# jtag-adapter-1-5.net
KiCad netlist of a schematic drawn in EAGLE
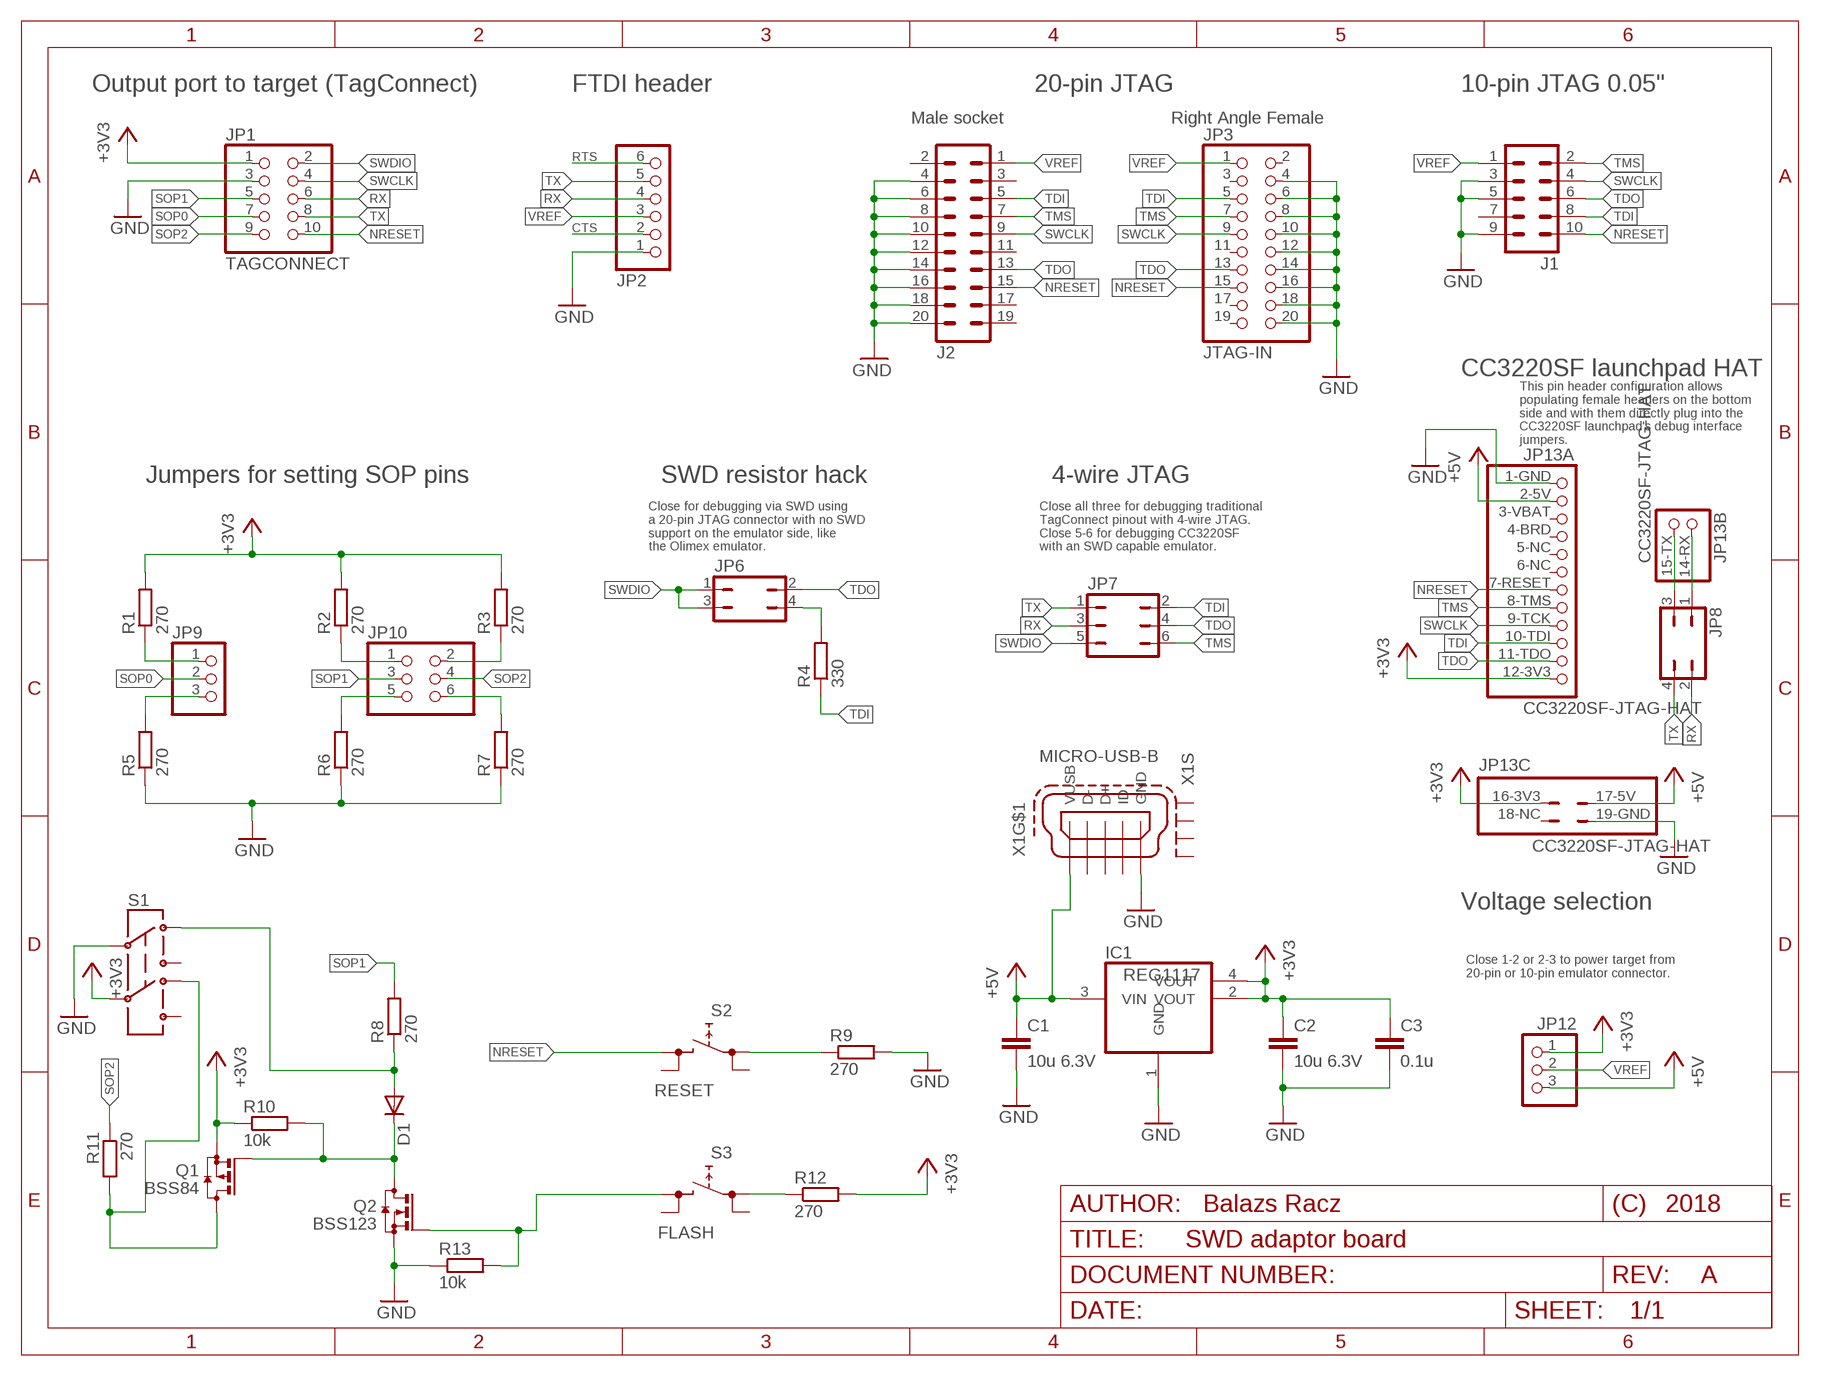
[diagram p0: schematic, sheet 1]

(export (version "E")
  (design (tool "Eeschema 10.0.6"))
  (components
    (comp (ref "C1")
      (value "10u 6.3V")
      (footprint "eagle-import:C0603K")
      (libsource (lib "eagle-import") (part "C-EUC0603K"))
    )
    (comp (ref "C2")
      (value "10u 6.3V")
      (footprint "eagle-import:C0603K")
      (libsource (lib "eagle-import") (part "C-EUC0603K"))
    )
    (comp (ref "C3")
      (value "0.1u")
      (footprint "eagle-import:C0603K")
      (libsource (lib "eagle-import") (part "C-EUC0603K"))
    )
    (comp (ref "D1")
      (value "DIODE-MINIMELF")
      (footprint "eagle-import:MINIMELF")
      (libsource (lib "eagle-import") (part "DIODE-MINIMELF"))
    )
    (comp (ref "IC1")
      (value "REG1117")
      (footprint "eagle-import:SOT223")
      (libsource (lib "eagle-import") (part "REG1117"))
    )
    (comp (ref "J1")
      (value "MA05-2_0.05X0.05")
      (footprint "eagle-import:MA05-2_0.05_X_0.05")
      (libsource (lib "eagle-import") (part "MA05-2_0.05X0.05"))
    )
    (comp (ref "J2")
      (value "MA10-2S")
      (footprint "eagle-import:MA10-2-SHROUDED")
      (libsource (lib "eagle-import") (part "MA10-2S"))
    )
    (comp (ref "JP1")
      (value "TAGCONNECT")
      (footprint "eagle-import:CON10M")
      (libsource (lib "eagle-import") (part "PINHD-2X5CN"))
    )
    (comp (ref "JP2")
      (value "PINHD-1X6")
      (footprint "eagle-import:1X06")
      (libsource (lib "eagle-import") (part "PINHD-1X6"))
    )
    (comp (ref "JP3")
      (value "JTAG-IN")
      (footprint "eagle-import:2X10_90")
      (libsource (lib "eagle-import") (part "PINHD-2X10/90"))
    )
    (comp (ref "JP6")
      (value "JP2Q")
      (footprint "eagle-import:JP2Q")
      (libsource (lib "eagle-import") (part "trainlib_JP2Q"))
    )
    (comp (ref "JP7")
      (value "JP3Q")
      (footprint "eagle-import:JP3Q")
      (libsource (lib "eagle-import") (part "JP3Q"))
    )
    (comp (ref "JP8")
      (value "JP2Q")
      (footprint "eagle-import:JP2Q")
      (libsource (lib "eagle-import") (part "JP2Q"))
    )
    (comp (ref "JP9")
      (value "PINHD-1X3")
      (footprint "eagle-import:1X03")
      (libsource (lib "eagle-import") (part "PINHD-1X3"))
    )
    (comp (ref "JP10")
      (value "PINHD-2X3")
      (footprint "eagle-import:2X03")
      (libsource (lib "eagle-import") (part "PINHD-2X3"))
    )
    (comp (ref "JP12")
      (value "PINHD-1X3")
      (footprint "eagle-import:1X03")
      (libsource (lib "eagle-import") (part "PINHD-1X3"))
    )
    (comp (ref "JP13")
      (value "CC3220SF-JTAG-HAT")
      (footprint "eagle-import:JTAG-LAUNCHPAD-3220SF")
      (libsource (lib "eagle-import") (part "CC3220SF-JTAG-HAT"))
    )
    (comp (ref "Q1")
      (value "BSS84")
      (footprint "eagle-import:SOT23")
      (libsource (lib "eagle-import") (part "BSS84"))
    )
    (comp (ref "Q2")
      (value "BSS123")
      (footprint "eagle-import:SOT23")
      (libsource (lib "eagle-import") (part "BSS123"))
    )
    (comp (ref "R1")
      (value "270")
      (footprint "eagle-import:R0805")
      (libsource (lib "eagle-import") (part "R-EU_R0805"))
    )
    (comp (ref "R2")
      (value "270")
      (footprint "eagle-import:R0805")
      (libsource (lib "eagle-import") (part "R-EU_R0805"))
    )
    (comp (ref "R3")
      (value "270")
      (footprint "eagle-import:R0805")
      (libsource (lib "eagle-import") (part "R-EU_R0805"))
    )
    (comp (ref "R4")
      (value "330")
      (footprint "eagle-import:R0805")
      (libsource (lib "eagle-import") (part "R-EU_R0805"))
    )
    (comp (ref "R5")
      (value "270")
      (footprint "eagle-import:R0805")
      (libsource (lib "eagle-import") (part "R-EU_R0805"))
    )
    (comp (ref "R6")
      (value "270")
      (footprint "eagle-import:R0805")
      (libsource (lib "eagle-import") (part "R-EU_R0805"))
    )
    (comp (ref "R7")
      (value "270")
      (footprint "eagle-import:R0805")
      (libsource (lib "eagle-import") (part "R-EU_R0805"))
    )
    (comp (ref "R8")
      (value "270")
      (footprint "eagle-import:R0805")
      (libsource (lib "eagle-import") (part "R-EU_R0805"))
    )
    (comp (ref "R9")
      (value "270")
      (footprint "eagle-import:R0805")
      (libsource (lib "eagle-import") (part "R-EU_R0805"))
    )
    (comp (ref "R10")
      (value "10k")
      (footprint "eagle-import:R0805")
      (libsource (lib "eagle-import") (part "R-EU_R0805"))
    )
    (comp (ref "R11")
      (value "270")
      (footprint "eagle-import:R0805")
      (libsource (lib "eagle-import") (part "R-EU_R0805"))
    )
    (comp (ref "R12")
      (value "270")
      (footprint "eagle-import:R0805")
      (libsource (lib "eagle-import") (part "R-EU_R0805"))
    )
    (comp (ref "R13")
      (value "10k")
      (footprint "eagle-import:R0805")
      (libsource (lib "eagle-import") (part "R-EU_R0805"))
    )
    (comp (ref "S1")
      (value "SWITCH-DPDTJS202011CQN")
      (footprint "eagle-import:DPDT-2.5X3.2MM")
      (libsource (lib "eagle-import") (part "SWITCH-DPDTJS202011CQN"))
    )
    (comp (ref "S2")
      (value "RESET")
      (footprint "eagle-import:TACTSW-6X6")
      (libsource (lib "eagle-import") (part "TACTSW-6X6S"))
    )
    (comp (ref "S3")
      (value "FLASH")
      (footprint "eagle-import:TACTSW-6X6")
      (libsource (lib "eagle-import") (part "TACTSW-6X6S"))
    )
    (comp (ref "X1")
      (value "MICRO-USB-B")
      (footprint "eagle-import:MICRO-B-PAC")
      (libsource (lib "eagle-import") (part "MICRO-USB-B"))
    )
  )
  (nets
    (net (code "1") (name "+3V3") (class "Default")
      (node (ref "C2") (pin "1") (pinfunction "1_1") (pintype "passive"))
      (node (ref "C3") (pin "1") (pinfunction "1_1") (pintype "passive"))
      (node (ref "IC1") (pin "2") (pinfunction "VOUT_2") (pintype "output"))
      (node (ref "IC1") (pin "4") (pinfunction "VOUT_4") (pintype "output"))
      (node (ref "JP1") (pin "1") (pinfunction "1_1") (pintype "passive"))
      (node (ref "JP12") (pin "1") (pinfunction "1_1") (pintype "passive"))
      (node (ref "JP13") (pin "12-3V3") (pinfunction "12_12-3V3") (pintype "passive"))
      (node (ref "JP13") (pin "16-3V3") (pinfunction "1_16-3V3") (pintype "passive"))
      (node (ref "Q1") (pin "2") (pinfunction "S_2") (pintype "passive"))
      (node (ref "R1") (pin "2") (pinfunction "2_2") (pintype "passive"))
      (node (ref "R10") (pin "1") (pinfunction "1_1") (pintype "passive"))
      (node (ref "R12") (pin "2") (pinfunction "2_2") (pintype "passive"))
      (node (ref "R2") (pin "2") (pinfunction "2_2") (pintype "passive"))
      (node (ref "R3") (pin "2") (pinfunction "2_2") (pintype "passive"))
      (node (ref "S1") (pin "5") (pinfunction "2C_5") (pintype "bidirectional"))
    )
    (net (code "2") (name "+5V") (class "Default")
      (node (ref "C1") (pin "1") (pinfunction "1_1") (pintype "passive"))
      (node (ref "IC1") (pin "3") (pinfunction "VIN_3") (pintype "input"))
      (node (ref "JP12") (pin "3") (pinfunction "3_3") (pintype "passive"))
      (node (ref "JP13") (pin "17-5V") (pinfunction "2_17-5V") (pintype "passive"))
      (node (ref "JP13") (pin "2-5V") (pinfunction "2_2-5V") (pintype "passive"))
      (node (ref "X1") (pin "1") (pinfunction "VUSB_1") (pintype "passive"))
    )
    (net (code "3") (name "/CTS") (class "Default")
      (node (ref "JP2") (pin "2") (pinfunction "2_2") (pintype "passive"))
    )
    (net (code "4") (name "/RTS") (class "Default")
      (node (ref "JP2") (pin "6") (pinfunction "6_6") (pintype "passive"))
    )
    (net (code "5") (name "GND") (class "Default")
      (node (ref "C1") (pin "2") (pinfunction "2_2") (pintype "passive"))
      (node (ref "C2") (pin "2") (pinfunction "2_2") (pintype "passive"))
      (node (ref "C3") (pin "2") (pinfunction "2_2") (pintype "passive"))
      (node (ref "IC1") (pin "1") (pinfunction "GND_1") (pintype "power_in"))
      (node (ref "J1") (pin "3") (pinfunction "3_3") (pintype "passive"))
      (node (ref "J1") (pin "5") (pinfunction "5_5") (pintype "passive"))
      (node (ref "J1") (pin "9") (pinfunction "9_9") (pintype "passive"))
      (node (ref "J2") (pin "10") (pinfunction "10_10") (pintype "passive"))
      (node (ref "J2") (pin "12") (pinfunction "12_12") (pintype "passive"))
      (node (ref "J2") (pin "14") (pinfunction "14_14") (pintype "passive"))
      (node (ref "J2") (pin "16") (pinfunction "16_16") (pintype "passive"))
      (node (ref "J2") (pin "18") (pinfunction "18_18") (pintype "passive"))
      (node (ref "J2") (pin "20") (pinfunction "20_20") (pintype "passive"))
      (node (ref "J2") (pin "4") (pinfunction "4_4") (pintype "passive"))
      (node (ref "J2") (pin "6") (pinfunction "6_6") (pintype "passive"))
      (node (ref "J2") (pin "8") (pinfunction "8_8") (pintype "passive"))
      (node (ref "JP1") (pin "3") (pinfunction "3_3") (pintype "passive"))
      (node (ref "JP13") (pin "1-GND") (pinfunction "1_1-GND") (pintype "passive"))
      (node (ref "JP13") (pin "19-GND") (pinfunction "4_19-GND") (pintype "passive"))
      (node (ref "JP2") (pin "1") (pinfunction "1_1") (pintype "passive"))
      (node (ref "JP3") (pin "10") (pinfunction "10_10") (pintype "passive"))
      (node (ref "JP3") (pin "12") (pinfunction "12_12") (pintype "passive"))
      (node (ref "JP3") (pin "14") (pinfunction "14_14") (pintype "passive"))
      (node (ref "JP3") (pin "16") (pinfunction "16_16") (pintype "passive"))
      (node (ref "JP3") (pin "18") (pinfunction "18_18") (pintype "passive"))
      (node (ref "JP3") (pin "20") (pinfunction "20_20") (pintype "passive"))
      (node (ref "JP3") (pin "4") (pinfunction "4_4") (pintype "passive"))
      (node (ref "JP3") (pin "6") (pinfunction "6_6") (pintype "passive"))
      (node (ref "JP3") (pin "8") (pinfunction "8_8") (pintype "passive"))
      (node (ref "Q2") (pin "2") (pinfunction "S_2") (pintype "passive"))
      (node (ref "R13") (pin "1") (pinfunction "1_1") (pintype "passive"))
      (node (ref "R5") (pin "1") (pinfunction "1_1") (pintype "passive"))
      (node (ref "R6") (pin "1") (pinfunction "1_1") (pintype "passive"))
      (node (ref "R7") (pin "1") (pinfunction "1_1") (pintype "passive"))
      (node (ref "R9") (pin "2") (pinfunction "2_2") (pintype "passive"))
      (node (ref "S1") (pin "2") (pinfunction "1C_2") (pintype "bidirectional"))
      (node (ref "X1") (pin "5") (pinfunction "GND_5") (pintype "passive"))
    )
    (net (code "6") (name "NRESET") (class "Default")
      (node (ref "J1") (pin "10") (pinfunction "10_10") (pintype "passive"))
      (node (ref "J2") (pin "15") (pinfunction "15_15") (pintype "passive"))
      (node (ref "JP1") (pin "10") (pinfunction "10_10") (pintype "passive"))
      (node (ref "JP13") (pin "7-RESET") (pinfunction "7_7-RESET") (pintype "passive"))
      (node (ref "JP3") (pin "15") (pinfunction "15_15") (pintype "passive"))
      (node (ref "S2") (pin "3") (pinfunction "2.1_3") (pintype "passive"))
    )
    (net (code "7") (name "Net-(JP6-Pad4)") (class "Default")
      (node (ref "JP6") (pin "4") (pinfunction "4_4") (pintype "passive"))
      (node (ref "R4") (pin "2") (pinfunction "2_2") (pintype "passive"))
    )
    (net (code "8") (name "Net-(JP9-Pad1)") (class "Default")
      (node (ref "JP9") (pin "1") (pinfunction "1_1") (pintype "passive"))
      (node (ref "R1") (pin "1") (pinfunction "1_1") (pintype "passive"))
    )
    (net (code "9") (name "Net-(JP9-Pad3)") (class "Default")
      (node (ref "JP9") (pin "3") (pinfunction "3_3") (pintype "passive"))
      (node (ref "R5") (pin "2") (pinfunction "2_2") (pintype "passive"))
    )
    (net (code "10") (name "Net-(JP10-Pad1)") (class "Default")
      (node (ref "JP10") (pin "1") (pinfunction "1_1") (pintype "passive"))
      (node (ref "R2") (pin "1") (pinfunction "1_1") (pintype "passive"))
    )
    (net (code "11") (name "Net-(JP10-Pad2)") (class "Default")
      (node (ref "JP10") (pin "2") (pinfunction "2_2") (pintype "passive"))
      (node (ref "R3") (pin "1") (pinfunction "1_1") (pintype "passive"))
    )
    (net (code "12") (name "Net-(JP10-Pad5)") (class "Default")
      (node (ref "JP10") (pin "5") (pinfunction "5_5") (pintype "passive"))
      (node (ref "R6") (pin "2") (pinfunction "2_2") (pintype "passive"))
    )
    (net (code "13") (name "Net-(JP10-Pad6)") (class "Default")
      (node (ref "JP10") (pin "6") (pinfunction "6_6") (pintype "passive"))
      (node (ref "R7") (pin "2") (pinfunction "2_2") (pintype "passive"))
    )
    (net (code "14") (name "Net-(JP13B-1)") (class "Default")
      (node (ref "JP13") (pin "14-RX") (pinfunction "1_14-RX") (pintype "passive"))
      (node (ref "JP8") (pin "1") (pinfunction "1_1") (pintype "passive"))
    )
    (net (code "15") (name "Net-(JP13B-2)") (class "Default")
      (node (ref "JP13") (pin "15-TX") (pinfunction "2_15-TX") (pintype "passive"))
      (node (ref "JP8") (pin "3") (pinfunction "3_3") (pintype "passive"))
    )
    (net (code "16") (name "Net-(Q1-D)") (class "Default")
      (node (ref "Q1") (pin "3") (pinfunction "D_3") (pintype "passive"))
      (node (ref "R11") (pin "2") (pinfunction "2_2") (pintype "passive"))
      (node (ref "S1") (pin "4") (pinfunction "2A_4") (pintype "bidirectional"))
    )
    (net (code "17") (name "Net-(Q1-G)") (class "Default")
      (node (ref "D1") (pin "C") (pinfunction "C_C") (pintype "passive"))
      (node (ref "Q1") (pin "1") (pinfunction "G_1") (pintype "passive"))
      (node (ref "Q2") (pin "3") (pinfunction "D_3") (pintype "passive"))
      (node (ref "R10") (pin "2") (pinfunction "2_2") (pintype "passive"))
    )
    (net (code "18") (name "Net-(Q2-G)") (class "Default")
      (node (ref "Q2") (pin "1") (pinfunction "G_1") (pintype "passive"))
      (node (ref "R13") (pin "2") (pinfunction "2_2") (pintype "passive"))
      (node (ref "S3") (pin "3") (pinfunction "2.1_3") (pintype "passive"))
    )
    (net (code "19") (name "Net-(S1-1A)") (class "Default")
      (node (ref "D1") (pin "A") (pinfunction "A_A") (pintype "passive"))
      (node (ref "R8") (pin "1") (pinfunction "1_1") (pintype "passive"))
      (node (ref "S1") (pin "1") (pinfunction "1A_1") (pintype "bidirectional"))
    )
    (net (code "20") (name "Net-(S2-1.1)") (class "Default")
      (node (ref "R9") (pin "1") (pinfunction "1_1") (pintype "passive"))
      (node (ref "S2") (pin "1") (pinfunction "1.1_1") (pintype "passive"))
    )
    (net (code "21") (name "Net-(S3-1.1)") (class "Default")
      (node (ref "R12") (pin "1") (pinfunction "1_1") (pintype "passive"))
      (node (ref "S3") (pin "1") (pinfunction "1.1_1") (pintype "passive"))
    )
    (net (code "22") (name "RX") (class "Default")
      (node (ref "JP1") (pin "6") (pinfunction "6_6") (pintype "passive"))
      (node (ref "JP2") (pin "4") (pinfunction "4_4") (pintype "passive"))
      (node (ref "JP7") (pin "3") (pinfunction "3_3") (pintype "passive"))
      (node (ref "JP8") (pin "2") (pinfunction "2_2") (pintype "passive"))
    )
    (net (code "23") (name "SOP0") (class "Default")
      (node (ref "JP1") (pin "7") (pinfunction "7_7") (pintype "passive"))
      (node (ref "JP9") (pin "2") (pinfunction "2_2") (pintype "passive"))
    )
    (net (code "24") (name "SOP1") (class "Default")
      (node (ref "JP1") (pin "5") (pinfunction "5_5") (pintype "passive"))
      (node (ref "JP10") (pin "3") (pinfunction "3_3") (pintype "passive"))
      (node (ref "R8") (pin "2") (pinfunction "2_2") (pintype "passive"))
    )
    (net (code "25") (name "SOP2") (class "Default")
      (node (ref "JP1") (pin "9") (pinfunction "9_9") (pintype "passive"))
      (node (ref "JP10") (pin "4") (pinfunction "4_4") (pintype "passive"))
      (node (ref "R11") (pin "1") (pinfunction "1_1") (pintype "passive"))
    )
    (net (code "26") (name "SWCLK") (class "Default")
      (node (ref "J1") (pin "4") (pinfunction "4_4") (pintype "passive"))
      (node (ref "J2") (pin "9") (pinfunction "9_9") (pintype "passive"))
      (node (ref "JP1") (pin "4") (pinfunction "4_4") (pintype "passive"))
      (node (ref "JP13") (pin "9-TCK") (pinfunction "9_9-TCK") (pintype "passive"))
      (node (ref "JP3") (pin "9") (pinfunction "9_9") (pintype "passive"))
    )
    (net (code "27") (name "SWDIO") (class "Default")
      (node (ref "JP1") (pin "2") (pinfunction "2_2") (pintype "passive"))
      (node (ref "JP6") (pin "1") (pinfunction "1_1") (pintype "passive"))
      (node (ref "JP6") (pin "3") (pinfunction "3_3") (pintype "passive"))
      (node (ref "JP7") (pin "5") (pinfunction "5_5") (pintype "passive"))
    )
    (net (code "28") (name "TDI") (class "Default")
      (node (ref "J1") (pin "8") (pinfunction "8_8") (pintype "passive"))
      (node (ref "J2") (pin "5") (pinfunction "5_5") (pintype "passive"))
      (node (ref "JP13") (pin "10-TDI") (pinfunction "10_10-TDI") (pintype "passive"))
      (node (ref "JP3") (pin "5") (pinfunction "5_5") (pintype "passive"))
      (node (ref "JP7") (pin "2") (pinfunction "2_2") (pintype "passive"))
      (node (ref "R4") (pin "1") (pinfunction "1_1") (pintype "passive"))
    )
    (net (code "29") (name "TDO") (class "Default")
      (node (ref "J1") (pin "6") (pinfunction "6_6") (pintype "passive"))
      (node (ref "J2") (pin "13") (pinfunction "13_13") (pintype "passive"))
      (node (ref "JP13") (pin "11-TDO") (pinfunction "11_11-TDO") (pintype "passive"))
      (node (ref "JP3") (pin "13") (pinfunction "13_13") (pintype "passive"))
      (node (ref "JP6") (pin "2") (pinfunction "2_2") (pintype "passive"))
      (node (ref "JP7") (pin "4") (pinfunction "4_4") (pintype "passive"))
    )
    (net (code "30") (name "TMS") (class "Default")
      (node (ref "J1") (pin "2") (pinfunction "2_2") (pintype "passive"))
      (node (ref "J2") (pin "7") (pinfunction "7_7") (pintype "passive"))
      (node (ref "JP13") (pin "8-TMS") (pinfunction "8_8-TMS") (pintype "passive"))
      (node (ref "JP3") (pin "7") (pinfunction "7_7") (pintype "passive"))
      (node (ref "JP7") (pin "6") (pinfunction "6_6") (pintype "passive"))
    )
    (net (code "31") (name "TX") (class "Default")
      (node (ref "JP1") (pin "8") (pinfunction "8_8") (pintype "passive"))
      (node (ref "JP2") (pin "5") (pinfunction "5_5") (pintype "passive"))
      (node (ref "JP7") (pin "1") (pinfunction "1_1") (pintype "passive"))
      (node (ref "JP8") (pin "4") (pinfunction "4_4") (pintype "passive"))
    )
    (net (code "32") (name "VREF") (class "Default")
      (node (ref "J1") (pin "1") (pinfunction "1_1") (pintype "passive"))
      (node (ref "J2") (pin "1") (pinfunction "1_1") (pintype "passive"))
      (node (ref "JP12") (pin "2") (pinfunction "2_2") (pintype "passive"))
      (node (ref "JP2") (pin "3") (pinfunction "3_3") (pintype "passive"))
      (node (ref "JP3") (pin "1") (pinfunction "1_1") (pintype "passive"))
    )
    (net (code "33") (name "unconnected-(J1-Pad7)") (class "Default")
      (node (ref "J1") (pin "7") (pinfunction "7_7") (pintype "passive"))
    )
    (net (code "34") (name "unconnected-(J2-Pad2)") (class "Default")
      (node (ref "J2") (pin "2") (pinfunction "2_2") (pintype "passive"))
    )
    (net (code "35") (name "unconnected-(J2-Pad3)") (class "Default")
      (node (ref "J2") (pin "3") (pinfunction "3_3") (pintype "passive"))
    )
    (net (code "36") (name "unconnected-(J2-Pad11)") (class "Default")
      (node (ref "J2") (pin "11") (pinfunction "11_11") (pintype "passive"))
    )
    (net (code "37") (name "unconnected-(J2-Pad17)") (class "Default")
      (node (ref "J2") (pin "17") (pinfunction "17_17") (pintype "passive"))
    )
    (net (code "38") (name "unconnected-(J2-Pad19)") (class "Default")
      (node (ref "J2") (pin "19") (pinfunction "19_19") (pintype "passive"))
    )
    (net (code "39") (name "unconnected-(JP3-Pad2)") (class "Default")
      (node (ref "JP3") (pin "2") (pinfunction "2_2") (pintype "passive"))
    )
    (net (code "40") (name "unconnected-(JP3-Pad3)") (class "Default")
      (node (ref "JP3") (pin "3") (pinfunction "3_3") (pintype "passive"))
    )
    (net (code "41") (name "unconnected-(JP3-Pad11)") (class "Default")
      (node (ref "JP3") (pin "11") (pinfunction "11_11") (pintype "passive"))
    )
    (net (code "42") (name "unconnected-(JP3-Pad17)") (class "Default")
      (node (ref "JP3") (pin "17") (pinfunction "17_17") (pintype "passive"))
    )
    (net (code "43") (name "unconnected-(JP3-Pad19)") (class "Default")
      (node (ref "JP3") (pin "19") (pinfunction "19_19") (pintype "passive"))
    )
    (net (code "44") (name "unconnected-(JP13A-3-Pad3-VBAT)") (class "Default")
      (node (ref "JP13") (pin "3-VBAT") (pinfunction "3_3-VBAT") (pintype "passive"))
    )
    (net (code "45") (name "unconnected-(JP13A-4-Pad4-BRD)") (class "Default")
      (node (ref "JP13") (pin "4-BRD") (pinfunction "4_4-BRD") (pintype "passive"))
    )
    (net (code "46") (name "unconnected-(JP13A-5-Pad5-NC)") (class "Default")
      (node (ref "JP13") (pin "5-NC") (pinfunction "5_5-NC") (pintype "passive"))
    )
    (net (code "47") (name "unconnected-(JP13A-6-Pad6-NC)") (class "Default")
      (node (ref "JP13") (pin "6-NC") (pinfunction "6_6-NC") (pintype "passive"))
    )
    (net (code "48") (name "unconnected-(JP13C-3-Pad18-NC)") (class "Default")
      (node (ref "JP13") (pin "18-NC") (pinfunction "3_18-NC") (pintype "passive"))
    )
    (net (code "49") (name "unconnected-(S1-1B-Pad3)") (class "Default")
      (node (ref "S1") (pin "3") (pinfunction "1B_3") (pintype "bidirectional"))
    )
    (net (code "50") (name "unconnected-(S1-2B-Pad6)") (class "Default")
      (node (ref "S1") (pin "6") (pinfunction "2B_6") (pintype "bidirectional"))
    )
    (net (code "51") (name "unconnected-(S2-1.2-Pad2)") (class "Default")
      (node (ref "S2") (pin "2") (pinfunction "1.2_2") (pintype "passive"))
    )
    (net (code "52") (name "unconnected-(S2-2.2-Pad4)") (class "Default")
      (node (ref "S2") (pin "4") (pinfunction "2.2_4") (pintype "passive"))
    )
    (net (code "53") (name "unconnected-(S3-1.2-Pad2)") (class "Default")
      (node (ref "S3") (pin "2") (pinfunction "1.2_2") (pintype "passive"))
    )
    (net (code "54") (name "unconnected-(S3-2.2-Pad4)") (class "Default")
      (node (ref "S3") (pin "4") (pinfunction "2.2_4") (pintype "passive"))
    )
    (net (code "55") (name "unconnected-(X1A-D+-Pad3)") (class "Default")
      (node (ref "X1") (pin "3") (pinfunction "D+_3") (pintype "passive"))
    )
    (net (code "56") (name "unconnected-(X1A-D--Pad2)") (class "Default")
      (node (ref "X1") (pin "2") (pinfunction "D-_2") (pintype "passive"))
    )
    (net (code "57") (name "unconnected-(X1A-ID-Pad4)") (class "Default")
      (node (ref "X1") (pin "4") (pinfunction "ID_4") (pintype "passive"))
    )
    (net (code "58") (name "unconnected-(X1B-S1-PadM1)") (class "Default")
      (node (ref "X1") (pin "M1") (pinfunction "S1_M1") (pintype "passive"))
    )
    (net (code "59") (name "unconnected-(X1B-S2-PadM2)") (class "Default")
      (node (ref "X1") (pin "M2") (pinfunction "S2_M2") (pintype "passive"))
    )
    (net (code "60") (name "unconnected-(X1B-S3-PadM3)") (class "Default")
      (node (ref "X1") (pin "M3") (pinfunction "S3_M3") (pintype "passive"))
    )
    (net (code "61") (name "unconnected-(X1B-S4-PadM4)") (class "Default")
      (node (ref "X1") (pin "M4") (pinfunction "S4_M4") (pintype "passive"))
    )
  )
)
